# PSU.net
KiCad netlist of a schematic drawn in Altium Designer
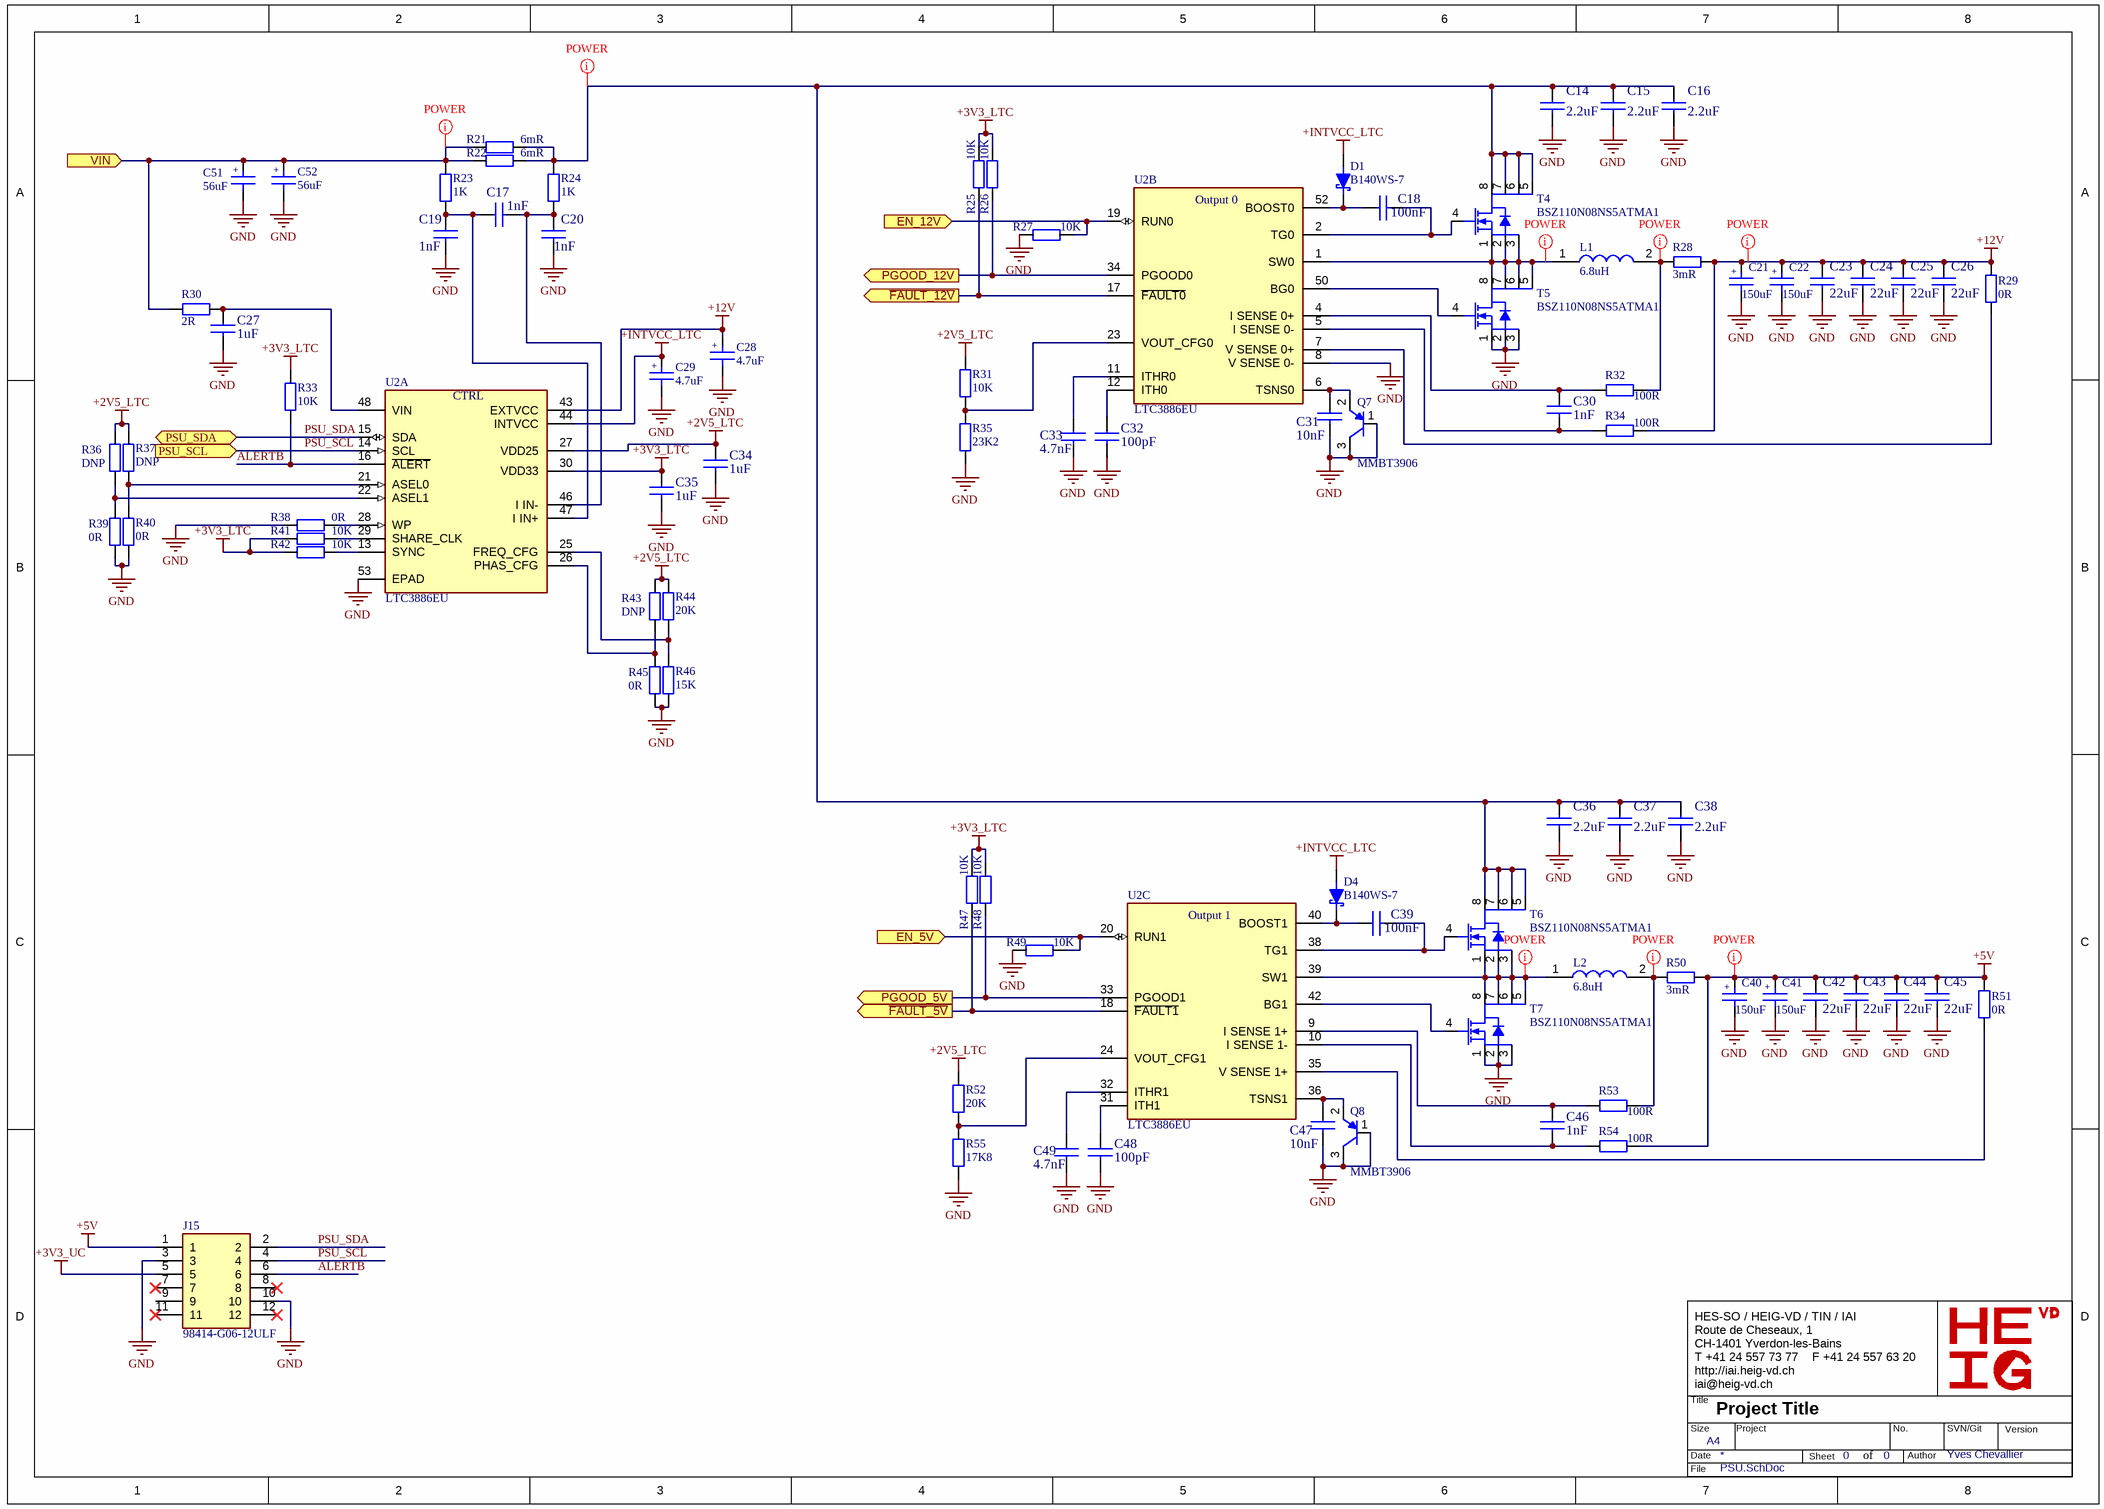
[diagram p0: PSU.SchDoc]

(export (version "E")
  (design (tool "Eeschema 10.0.6"))
  (components
    (comp (ref "C14")
      (value "2.2uF")
      (footprint "SM/C_0805")
      (description "CAP CER 2.2UF 25V X5R 0805")
      (fields (field (name "MANUFACTURER") "Samsung") (field (name "VOLTAGE") "25V"))
      (libsource (lib "Battery_PSU") (part "CAP CER 2.2UF 25V X5R 0805"))
    )
    (comp (ref "C15")
      (value "2.2uF")
      (footprint "SM/C_0805")
      (description "CAP CER 2.2UF 25V X5R 0805")
      (fields (field (name "MANUFACTURER") "Samsung") (field (name "VOLTAGE") "25V"))
      (libsource (lib "Battery_PSU") (part "CAP CER 2.2UF 25V X5R 0805"))
    )
    (comp (ref "C16")
      (value "2.2uF")
      (footprint "SM/C_0805")
      (description "CAP CER 2.2UF 25V X5R 0805")
      (fields (field (name "MANUFACTURER") "Samsung") (field (name "VOLTAGE") "25V"))
      (libsource (lib "Battery_PSU") (part "CAP CER 2.2UF 25V X5R 0805"))
    )
    (comp (ref "C17")
      (value "1nF")
      (footprint "SM/C_0603")
      (description "CAP CER 1NF 50V X7R 0603")
      (fields (field (name "MANUFACTURER") "Samsung") (field (name "VOLTAGE") "50V"))
      (libsource (lib "Battery_PSU") (part "CAP CER 1NF 50V X7R 0603"))
    )
    (comp (ref "C18")
      (value "100nF")
      (footprint "SM/C_0603")
      (description "CAP CER 0.1UF 50V X7R 0603")
      (fields (field (name "MANUFACTURER") "Samsung") (field (name "TOLERANCE") "10%"))
      (libsource (lib "Battery_PSU") (part "CAP CER 0.1UF 50V X7R 0603"))
    )
    (comp (ref "C19")
      (value "1nF")
      (footprint "SM/C_0603")
      (description "CAP CER 1NF 50V X7R 0603")
      (fields (field (name "MANUFACTURER") "Samsung") (field (name "VOLTAGE") "50V"))
      (libsource (lib "Battery_PSU") (part "CAP CER 1NF 50V X7R 0603"))
    )
    (comp (ref "C20")
      (value "1nF")
      (footprint "SM/C_0603")
      (description "CAP CER 1NF 50V X7R 0603")
      (fields (field (name "MANUFACTURER") "Samsung") (field (name "VOLTAGE") "50V"))
      (libsource (lib "Battery_PSU") (part "CAP CER 1NF 50V X7R 0603"))
    )
    (comp (ref "C21")
      (value "150uF")
      (footprint "SM/CT_7343_12_D")
      (description "CAP TANT 150UF 20% 25V 2924")
      (fields (field (name "TOLERANCE") "20%") (field (name "MANUFACTURER") "AVX"))
      (libsource (lib "Battery_PSU") (part "CAP TANT 150UF 20% 25V 2924"))
    )
    (comp (ref "C22")
      (value "150uF")
      (footprint "SM/CT_7343_12_D")
      (description "CAP TANT 150UF 20% 25V 2924")
      (fields (field (name "TOLERANCE") "20%") (field (name "MANUFACTURER") "AVX"))
      (libsource (lib "Battery_PSU") (part "CAP TANT 150UF 20% 25V 2924"))
    )
    (comp (ref "C23")
      (value "22uF")
      (footprint "SM/C_1210")
      (description "CAP CER 22UF 25V X5R 1210")
      (fields (field (name "MANUFACTURER") "Samsung") (field (name "VOLTAGE") "25V"))
      (libsource (lib "Battery_PSU") (part "CAP CER 22UF 25V X5R 1210"))
    )
    (comp (ref "C24")
      (value "22uF")
      (footprint "SM/C_1210")
      (description "CAP CER 22UF 25V X5R 1210")
      (fields (field (name "MANUFACTURER") "Samsung") (field (name "VOLTAGE") "25V"))
      (libsource (lib "Battery_PSU") (part "CAP CER 22UF 25V X5R 1210"))
    )
    (comp (ref "C25")
      (value "22uF")
      (footprint "SM/C_1210")
      (description "CAP CER 22UF 25V X5R 1210")
      (fields (field (name "MANUFACTURER") "Samsung") (field (name "VOLTAGE") "25V"))
      (libsource (lib "Battery_PSU") (part "CAP CER 22UF 25V X5R 1210"))
    )
    (comp (ref "C26")
      (value "22uF")
      (footprint "SM/C_1210")
      (description "CAP CER 22UF 25V X5R 1210")
      (fields (field (name "MANUFACTURER") "Samsung") (field (name "VOLTAGE") "25V"))
      (libsource (lib "Battery_PSU") (part "CAP CER 22UF 25V X5R 1210"))
    )
    (comp (ref "C27")
      (value "1uF")
      (footprint "SM/C_0805")
      (description "CAP CER 1UF 25V X7R 0805")
      (fields (field (name "MANUFACTURER") "Yageo") (field (name "VOLTAGE") "25V"))
      (libsource (lib "Battery_PSU") (part "CAP CER 1UF 25V X7R 0805"))
    )
    (comp (ref "C28")
      (value "4.7uF")
      (footprint "T_CAPMP3216X180N")
      (description "Capacitor TA 4.7uF 10V 20% 3216")
      (fields (field (name "TOLERANCE") "20%") (field (name "MANUFACTURER") "Kemet"))
      (libsource (lib "Battery_PSU") (part "C-TA-4.7uF-10V-20%-3216"))
    )
    (comp (ref "C29")
      (value "4.7uF")
      (footprint "T_CAPMP3216X180N")
      (description "Capacitor TA 4.7uF 10V 20% 3216")
      (fields (field (name "TOLERANCE") "20%") (field (name "MANUFACTURER") "Kemet"))
      (libsource (lib "Battery_PSU") (part "C-TA-4.7uF-10V-20%-3216"))
    )
    (comp (ref "C30")
      (value "1nF")
      (footprint "SM/C_0603")
      (description "CAP CER 1NF 50V X7R 0603")
      (fields (field (name "MANUFACTURER") "Samsung") (field (name "VOLTAGE") "50V"))
      (libsource (lib "Battery_PSU") (part "CAP CER 1NF 50V X7R 0603"))
    )
    (comp (ref "C31")
      (value "10nF")
      (footprint "SM/C_0603")
      (description "CAP CER 10NF 50V X7R 0603")
      (fields (field (name "MANUFACTURER") "Samsung") (field (name "VOLTAGE") "50V"))
      (libsource (lib "Battery_PSU") (part "CAP CER 10NF 50V X7R 0603"))
    )
    (comp (ref "C32")
      (value "100pF")
      (footprint "SM/C_0603")
      (description "CAP CER 100PF 50V C0G/NP0 0603")
      (fields (field (name "MANUFACTURER") "Samsung") (field (name "VOLTAGE") "50V"))
      (libsource (lib "Battery_PSU") (part "CAP CER 100PF 50V C0G/NP0 0603"))
    )
    (comp (ref "C33")
      (value "4.7nF")
      (footprint "SM/C_0603")
      (description "CAP CER 4700PF 50V X7R 0603")
      (fields (field (name "MANUFACTURER") "Kemet") (field (name "VOLTAGE") "50V"))
      (libsource (lib "Battery_PSU") (part "CAP CER 4700PF 50V X7R 0603"))
    )
    (comp (ref "C34")
      (value "1uF")
      (footprint "SM/C_0603")
      (description "CAP CER 1UF 10V X7R 0603")
      (fields (field (name "MANUFACTURER") "Samsung") (field (name "TOLERANCE") "10%"))
      (libsource (lib "Battery_PSU") (part "CAP CER 1UF 10V X7R 0603"))
    )
    (comp (ref "C35")
      (value "1uF")
      (footprint "SM/C_0603")
      (description "CAP CER 1UF 10V X7R 0603")
      (fields (field (name "MANUFACTURER") "Samsung") (field (name "TOLERANCE") "10%"))
      (libsource (lib "Battery_PSU") (part "CAP CER 1UF 10V X7R 0603"))
    )
    (comp (ref "C36")
      (value "2.2uF")
      (footprint "SM/C_0805")
      (description "CAP CER 2.2UF 25V X5R 0805")
      (fields (field (name "MANUFACTURER") "Samsung") (field (name "VOLTAGE") "25V"))
      (libsource (lib "Battery_PSU") (part "CAP CER 2.2UF 25V X5R 0805"))
    )
    (comp (ref "C37")
      (value "2.2uF")
      (footprint "SM/C_0805")
      (description "CAP CER 2.2UF 25V X5R 0805")
      (fields (field (name "MANUFACTURER") "Samsung") (field (name "VOLTAGE") "25V"))
      (libsource (lib "Battery_PSU") (part "CAP CER 2.2UF 25V X5R 0805"))
    )
    (comp (ref "C38")
      (value "2.2uF")
      (footprint "SM/C_0805")
      (description "CAP CER 2.2UF 25V X5R 0805")
      (fields (field (name "MANUFACTURER") "Samsung") (field (name "VOLTAGE") "25V"))
      (libsource (lib "Battery_PSU") (part "CAP CER 2.2UF 25V X5R 0805"))
    )
    (comp (ref "C39")
      (value "100nF")
      (footprint "SM/C_0603")
      (description "CAP CER 0.1UF 50V X7R 0603")
      (fields (field (name "MANUFACTURER") "Samsung") (field (name "TOLERANCE") "10%"))
      (libsource (lib "Battery_PSU") (part "CAP CER 0.1UF 50V X7R 0603"))
    )
    (comp (ref "C40")
      (value "150uF")
      (footprint "SM/CT_7343_12_D")
      (description "CAP TANT 150UF 20% 25V 2924")
      (fields (field (name "TOLERANCE") "20%") (field (name "MANUFACTURER") "AVX"))
      (libsource (lib "Battery_PSU") (part "CAP TANT 150UF 20% 25V 2924"))
    )
    (comp (ref "C41")
      (value "150uF")
      (footprint "SM/CT_7343_12_D")
      (description "CAP TANT 150UF 20% 25V 2924")
      (fields (field (name "TOLERANCE") "20%") (field (name "MANUFACTURER") "AVX"))
      (libsource (lib "Battery_PSU") (part "CAP TANT 150UF 20% 25V 2924"))
    )
    (comp (ref "C42")
      (value "22uF")
      (footprint "SM/C_1210")
      (description "CAP CER 22UF 25V X5R 1210")
      (fields (field (name "MANUFACTURER") "Samsung") (field (name "VOLTAGE") "25V"))
      (libsource (lib "Battery_PSU") (part "CAP CER 22UF 25V X5R 1210"))
    )
    (comp (ref "C43")
      (value "22uF")
      (footprint "SM/C_1210")
      (description "CAP CER 22UF 25V X5R 1210")
      (fields (field (name "MANUFACTURER") "Samsung") (field (name "VOLTAGE") "25V"))
      (libsource (lib "Battery_PSU") (part "CAP CER 22UF 25V X5R 1210"))
    )
    (comp (ref "C44")
      (value "22uF")
      (footprint "SM/C_1210")
      (description "CAP CER 22UF 25V X5R 1210")
      (fields (field (name "MANUFACTURER") "Samsung") (field (name "VOLTAGE") "25V"))
      (libsource (lib "Battery_PSU") (part "CAP CER 22UF 25V X5R 1210"))
    )
    (comp (ref "C45")
      (value "22uF")
      (footprint "SM/C_1210")
      (description "CAP CER 22UF 25V X5R 1210")
      (fields (field (name "MANUFACTURER") "Samsung") (field (name "VOLTAGE") "25V"))
      (libsource (lib "Battery_PSU") (part "CAP CER 22UF 25V X5R 1210"))
    )
    (comp (ref "C46")
      (value "1nF")
      (footprint "SM/C_0603")
      (description "CAP CER 1NF 50V X7R 0603")
      (fields (field (name "MANUFACTURER") "Samsung") (field (name "VOLTAGE") "50V"))
      (libsource (lib "Battery_PSU") (part "CAP CER 1NF 50V X7R 0603"))
    )
    (comp (ref "C47")
      (value "10nF")
      (footprint "SM/C_0603")
      (description "CAP CER 10NF 50V X7R 0603")
      (fields (field (name "MANUFACTURER") "Samsung") (field (name "VOLTAGE") "50V"))
      (libsource (lib "Battery_PSU") (part "CAP CER 10NF 50V X7R 0603"))
    )
    (comp (ref "C48")
      (value "100pF")
      (footprint "SM/C_0603")
      (description "CAP CER 100PF 50V C0G/NP0 0603")
      (fields (field (name "MANUFACTURER") "Samsung") (field (name "VOLTAGE") "50V"))
      (libsource (lib "Battery_PSU") (part "CAP CER 100PF 50V C0G/NP0 0603"))
    )
    (comp (ref "C49")
      (value "4.7nF")
      (footprint "SM/C_0603")
      (description "CAP CER 4700PF 50V X7R 0603")
      (fields (field (name "MANUFACTURER") "Kemet") (field (name "VOLTAGE") "50V"))
      (libsource (lib "Battery_PSU") (part "CAP CER 4700PF 50V X7R 0603"))
    )
    (comp (ref "C51")
      (value "56uF")
      (footprint "SM/C SIZE F12")
      (description "HYBRID POLYMER, SMD, 63V, 56UF,")
      (fields (field (name "TOLERANCE") "20%") (field (name "MANUFACTURER") "Kemet"))
      (libsource (lib "Battery_PSU") (part "HYBRID POLYMER, SMD, 63V, 56UF,"))
    )
    (comp (ref "C52")
      (value "56uF")
      (footprint "SM/C SIZE F12")
      (description "HYBRID POLYMER, SMD, 63V, 56UF,")
      (fields (field (name "TOLERANCE") "20%") (field (name "MANUFACTURER") "Kemet"))
      (libsource (lib "Battery_PSU") (part "HYBRID POLYMER, SMD, 63V, 56UF,"))
    )
    (comp (ref "D1")
      (value "B140WS-7")
      (footprint "SM/D_SOD323_A1C2 (SC-76)")
      (description "DIODE SCHOTTKY 40V 1A SOD323")
      (fields (field (name "MANUFACTURER") "Diodes Incorporated"))
      (libsource (lib "Battery_PSU") (part "DIODE SCHOTTKY 40V 1A SOD323"))
    )
    (comp (ref "D4")
      (value "B140WS-7")
      (footprint "SM/D_SOD323_A1C2 (SC-76)")
      (description "DIODE SCHOTTKY 40V 1A SOD323")
      (fields (field (name "MANUFACTURER") "Diodes Incorporated"))
      (libsource (lib "Battery_PSU") (part "DIODE SCHOTTKY 40V 1A SOD323"))
    )
    (comp (ref "J15")
      (value "98414-G06-12ULF")
      (footprint "98414G0612ULF")
      (description "CONN HEADER VERT 12POS 2MM")
      (fields (field (name "MANUFACTURER") "Amphenol"))
      (libsource (lib "Battery_PSU") (part "CONN HEADER VERT 12POS 2MM"))
    )
    (comp (ref "L1")
      (value "6.8uH")
      (footprint "SamacSys:WE-HCI_189023")
      (description "FIXED IND 6.8UH 18.5A 4.1MOHM SM")
      (fields (field (name "MANUFACTURER") "Wurth Elektronik"))
      (libsource (lib "Battery_PSU") (part "FIXED IND 6.8UH 18.5A 4.1MOHM SM"))
    )
    (comp (ref "L2")
      (value "6.8uH")
      (footprint "SamacSys:WE-HCI_189023")
      (description "FIXED IND 6.8UH 18.5A 4.1MOHM SM")
      (fields (field (name "MANUFACTURER") "Wurth Elektronik"))
      (libsource (lib "Battery_PSU") (part "FIXED IND 6.8UH 18.5A 4.1MOHM SM"))
    )
    (comp (ref "Q7")
      (value "MMBT3906")
      (footprint "SOT23")
      (description "TRANSISTOR, PNP, -40V, -0.2A, 10")
      (fields (field (name "MANUFACTURER") "Taiwan Semiconductor"))
      (libsource (lib "Battery_PSU") (part "TRANSISTOR, PNP, -40V, -0.2A, 10"))
    )
    (comp (ref "Q8")
      (value "MMBT3906")
      (footprint "SOT23")
      (description "TRANSISTOR, PNP, -40V, -0.2A, 10")
      (fields (field (name "MANUFACTURER") "Taiwan Semiconductor"))
      (libsource (lib "Battery_PSU") (part "TRANSISTOR, PNP, -40V, -0.2A, 10"))
    )
    (comp (ref "R21")
      (value "6mR")
      (footprint "SM/R_2512")
      (description "METAL CURRENT SENSOR 2512 1% 100")
      (fields (field (name "MANUFACTURER") "Yageo") (field (name "POWER") "2W"))
      (libsource (lib "Battery_PSU") (part "METAL CURRENT SENSOR 2512 1% 100"))
    )
    (comp (ref "R22")
      (value "6mR")
      (footprint "SM/R_2512")
      (description "METAL CURRENT SENSOR 2512 1% 100")
      (fields (field (name "MANUFACTURER") "Yageo") (field (name "POWER") "2W"))
      (libsource (lib "Battery_PSU") (part "METAL CURRENT SENSOR 2512 1% 100"))
    )
    (comp (ref "R23")
      (value "1K")
      (footprint "SM/R_0603")
      (description "RES SMD 1K OHM 1% 1/10W 0603")
      (fields (field (name "MANUFACTURER") "Yageo") (field (name "POWER") "100mW"))
      (libsource (lib "Battery_PSU") (part "RES SMD 1K OHM 1% 1/10W 0603"))
    )
    (comp (ref "R24")
      (value "1K")
      (footprint "SM/R_0603")
      (description "RES SMD 1K OHM 1% 1/10W 0603")
      (fields (field (name "MANUFACTURER") "Yageo") (field (name "POWER") "100mW"))
      (libsource (lib "Battery_PSU") (part "RES SMD 1K OHM 1% 1/10W 0603"))
    )
    (comp (ref "R25")
      (value "10K")
      (footprint "SM/R_0603")
      (description "Résistance 0603 100mW 1% 10K")
      (fields (field (name "MANUFACTURER") "Yageo") (field (name "POWER") "100mW"))
      (libsource (lib "Battery_PSU") (part "RES SMD 10K OHM 1% 1/10W 0603"))
    )
    (comp (ref "R26")
      (value "10K")
      (footprint "SM/R_0603")
      (description "Résistance 0603 100mW 1% 10K")
      (fields (field (name "MANUFACTURER") "Yageo") (field (name "POWER") "100mW"))
      (libsource (lib "Battery_PSU") (part "RES SMD 10K OHM 1% 1/10W 0603"))
    )
    (comp (ref "R27")
      (value "10K")
      (footprint "SM/R_0603")
      (description "Résistance 0603 100mW 1% 10K")
      (fields (field (name "MANUFACTURER") "Yageo") (field (name "POWER") "100mW"))
      (libsource (lib "Battery_PSU") (part "RES SMD 10K OHM 1% 1/10W 0603"))
    )
    (comp (ref "R28")
      (value "3mR")
      (footprint "SM/R_1210")
      (description "RES 0.003 OHM 5% 1W 1210")
      (fields (field (name "MANUFACTURER") "Rohm") (field (name "POWER") "1W"))
      (libsource (lib "Battery_PSU") (part "RES 0.003 OHM 5% 1W 1210"))
    )
    (comp (ref "R29")
      (value "0R")
      (footprint "SM/R_0603")
      (description "RES SMD 0 OHM JUMPER 1/10W 0603")
      (fields (field (name "MANUFACTURER") "Yageo") (field (name "POWER") "100mW"))
      (libsource (lib "Battery_PSU") (part "RES SMD 0 OHM JUMPER 1/10W 0603"))
    )
    (comp (ref "R30")
      (value "2R")
      (footprint "SM/R_0603")
      (description "RES 2 OHM 1% 1/10W 0603")
      (fields (field (name "MANUFACTURER") "Yageo") (field (name "POWER") "100mW"))
      (libsource (lib "Battery_PSU") (part "RES 2 OHM 1% 1/10W 0603"))
    )
    (comp (ref "R31")
      (value "10K")
      (footprint "SM/R_0603")
      (description "Résistance 0603 100mW 1% 10K")
      (fields (field (name "MANUFACTURER") "Yageo") (field (name "POWER") "100mW"))
      (libsource (lib "Battery_PSU") (part "RES SMD 10K OHM 1% 1/10W 0603"))
    )
    (comp (ref "R32")
      (value "100R")
      (footprint "SM/R_0603")
      (description "RES 100 OHM 1% 1/10W 0603")
      (fields (field (name "MANUFACTURER") "Yageo") (field (name "POWER") "100mW"))
      (libsource (lib "Battery_PSU") (part "RES 100 OHM 1% 1/10W 0603"))
    )
    (comp (ref "R33")
      (value "10K")
      (footprint "SM/R_0603")
      (description "Résistance 0603 100mW 1% 10K")
      (fields (field (name "MANUFACTURER") "Yageo") (field (name "POWER") "100mW"))
      (libsource (lib "Battery_PSU") (part "RES SMD 10K OHM 1% 1/10W 0603"))
    )
    (comp (ref "R34")
      (value "100R")
      (footprint "SM/R_0603")
      (description "RES 100 OHM 1% 1/10W 0603")
      (fields (field (name "MANUFACTURER") "Yageo") (field (name "POWER") "100mW"))
      (libsource (lib "Battery_PSU") (part "RES 100 OHM 1% 1/10W 0603"))
    )
    (comp (ref "R35")
      (value "23K2")
      (footprint "SM/R_0603")
      (description "RES 23.2K OHM 1% 1/10W 0603")
      (fields (field (name "MANUFACTURER") "Yageo") (field (name "POWER") "100mW"))
      (libsource (lib "Battery_PSU") (part "RES 23.2K OHM 1% 1/10W 0603"))
    )
    (comp (ref "R36")
      (value "DNP")
      (footprint "SM/R_0603")
      (description "RES SMD DNP JUMPER 1/10W 0603")
      (libsource (lib "Battery_PSU") (part "RES SMD DNP JUMPER 1/10W 0603"))
    )
    (comp (ref "R37")
      (value "DNP")
      (footprint "SM/R_0603")
      (description "RES SMD DNP JUMPER 1/10W 0603")
      (libsource (lib "Battery_PSU") (part "RES SMD DNP JUMPER 1/10W 0603"))
    )
    (comp (ref "R38")
      (value "0R")
      (footprint "SM/R_0603")
      (description "RES SMD 0 OHM JUMPER 1/10W 0603")
      (fields (field (name "MANUFACTURER") "Yageo") (field (name "POWER") "100mW"))
      (libsource (lib "Battery_PSU") (part "RES SMD 0 OHM JUMPER 1/10W 0603"))
    )
    (comp (ref "R39")
      (value "0R")
      (footprint "SM/R_0603")
      (description "RES SMD 0 OHM JUMPER 1/10W 0603")
      (fields (field (name "MANUFACTURER") "Yageo") (field (name "POWER") "100mW"))
      (libsource (lib "Battery_PSU") (part "RES SMD 0 OHM JUMPER 1/10W 0603"))
    )
    (comp (ref "R40")
      (value "0R")
      (footprint "SM/R_0603")
      (description "RES SMD 0 OHM JUMPER 1/10W 0603")
      (fields (field (name "MANUFACTURER") "Yageo") (field (name "POWER") "100mW"))
      (libsource (lib "Battery_PSU") (part "RES SMD 0 OHM JUMPER 1/10W 0603"))
    )
    (comp (ref "R41")
      (value "10K")
      (footprint "SM/R_0603")
      (description "Résistance 0603 100mW 1% 10K")
      (fields (field (name "MANUFACTURER") "Yageo") (field (name "POWER") "100mW"))
      (libsource (lib "Battery_PSU") (part "RES SMD 10K OHM 1% 1/10W 0603"))
    )
    (comp (ref "R42")
      (value "10K")
      (footprint "SM/R_0603")
      (description "Résistance 0603 100mW 1% 10K")
      (fields (field (name "MANUFACTURER") "Yageo") (field (name "POWER") "100mW"))
      (libsource (lib "Battery_PSU") (part "RES SMD 10K OHM 1% 1/10W 0603"))
    )
    (comp (ref "R43")
      (value "DNP")
      (footprint "SM/R_0603")
      (description "RES SMD DNP JUMPER 1/10W 0603")
      (libsource (lib "Battery_PSU") (part "RES SMD DNP JUMPER 1/10W 0603"))
    )
    (comp (ref "R44")
      (value "20K")
      (footprint "SM/R_0603")
      (description "RES 20K OHM 1% 1/10W 0603")
      (fields (field (name "MANUFACTURER") "Yageo") (field (name "POWER") "100mW"))
      (libsource (lib "Battery_PSU") (part "RES 20K OHM 1% 1/10W 0603"))
    )
    (comp (ref "R45")
      (value "0R")
      (footprint "SM/R_0603")
      (description "RES SMD 0 OHM JUMPER 1/10W 0603")
      (fields (field (name "MANUFACTURER") "Yageo") (field (name "POWER") "100mW"))
      (libsource (lib "Battery_PSU") (part "RES SMD 0 OHM JUMPER 1/10W 0603"))
    )
    (comp (ref "R46")
      (value "15K")
      (footprint "SM/R_0603")
      (description "RES 15K OHM 1% 1/10W 0603")
      (fields (field (name "MANUFACTURER") "Yageo") (field (name "POWER") "100mW"))
      (libsource (lib "Battery_PSU") (part "RES 15K OHM 1% 1/10W 0603"))
    )
    (comp (ref "R47")
      (value "10K")
      (footprint "SM/R_0603")
      (description "Résistance 0603 100mW 1% 10K")
      (fields (field (name "MANUFACTURER") "Yageo") (field (name "POWER") "100mW"))
      (libsource (lib "Battery_PSU") (part "RES SMD 10K OHM 1% 1/10W 0603"))
    )
    (comp (ref "R48")
      (value "10K")
      (footprint "SM/R_0603")
      (description "Résistance 0603 100mW 1% 10K")
      (fields (field (name "MANUFACTURER") "Yageo") (field (name "POWER") "100mW"))
      (libsource (lib "Battery_PSU") (part "RES SMD 10K OHM 1% 1/10W 0603"))
    )
    (comp (ref "R49")
      (value "10K")
      (footprint "SM/R_0603")
      (description "Résistance 0603 100mW 1% 10K")
      (fields (field (name "MANUFACTURER") "Yageo") (field (name "POWER") "100mW"))
      (libsource (lib "Battery_PSU") (part "RES SMD 10K OHM 1% 1/10W 0603"))
    )
    (comp (ref "R50")
      (value "3mR")
      (footprint "SM/R_1210")
      (description "RES 0.003 OHM 5% 1W 1210")
      (fields (field (name "MANUFACTURER") "Rohm") (field (name "POWER") "1W"))
      (libsource (lib "Battery_PSU") (part "RES 0.003 OHM 5% 1W 1210"))
    )
    (comp (ref "R51")
      (value "0R")
      (footprint "SM/R_0603")
      (description "RES SMD 0 OHM JUMPER 1/10W 0603")
      (fields (field (name "MANUFACTURER") "Yageo") (field (name "POWER") "100mW"))
      (libsource (lib "Battery_PSU") (part "RES SMD 0 OHM JUMPER 1/10W 0603"))
    )
    (comp (ref "R52")
      (value "20K")
      (footprint "SM/R_0603")
      (description "RES 20K OHM 1% 1/10W 0603")
      (fields (field (name "MANUFACTURER") "Yageo") (field (name "POWER") "100mW"))
      (libsource (lib "Battery_PSU") (part "RES 20K OHM 1% 1/10W 0603"))
    )
    (comp (ref "R53")
      (value "100R")
      (footprint "SM/R_0603")
      (description "RES 100 OHM 1% 1/10W 0603")
      (fields (field (name "MANUFACTURER") "Yageo") (field (name "POWER") "100mW"))
      (libsource (lib "Battery_PSU") (part "RES 100 OHM 1% 1/10W 0603"))
    )
    (comp (ref "R54")
      (value "100R")
      (footprint "SM/R_0603")
      (description "RES 100 OHM 1% 1/10W 0603")
      (fields (field (name "MANUFACTURER") "Yageo") (field (name "POWER") "100mW"))
      (libsource (lib "Battery_PSU") (part "RES 100 OHM 1% 1/10W 0603"))
    )
    (comp (ref "R55")
      (value "17K8")
      (footprint "SM/R_0603")
      (description "RES 17.8K OHM 1% 1/10W 0603")
      (fields (field (name "MANUFACTURER") "Yageo") (field (name "POWER") "100mW"))
      (libsource (lib "Battery_PSU") (part "RES 17.8K OHM 1% 1/10W 0603"))
    )
    (comp (ref "T4")
      (value "BSZ110N08NS5ATMA1")
      (footprint "BSZ110N08NS5ATMA1")
      (description "MOSFET N-CH 80V 40A TSDSON")
      (libsource (lib "Battery_PSU") (part "MOSFET N-CH 80V 40A TSDSON"))
    )
    (comp (ref "T5")
      (value "BSZ110N08NS5ATMA1")
      (footprint "BSZ110N08NS5ATMA1")
      (description "MOSFET N-CH 80V 40A TSDSON")
      (libsource (lib "Battery_PSU") (part "MOSFET N-CH 80V 40A TSDSON"))
    )
    (comp (ref "T6")
      (value "BSZ110N08NS5ATMA1")
      (footprint "BSZ110N08NS5ATMA1")
      (description "MOSFET N-CH 80V 40A TSDSON")
      (libsource (lib "Battery_PSU") (part "MOSFET N-CH 80V 40A TSDSON"))
    )
    (comp (ref "T7")
      (value "BSZ110N08NS5ATMA1")
      (footprint "BSZ110N08NS5ATMA1")
      (description "MOSFET N-CH 80V 40A TSDSON")
      (libsource (lib "Battery_PSU") (part "MOSFET N-CH 80V 40A TSDSON"))
    )
    (comp (ref "U2")
      (value "LTC3886EU")
      (footprint "UKG_52_ADI")
      (description "IC REG CTRLR BUCK PMBUS 52QFN")
      (fields (field (name "MANUFACTURER") "Analog Devices"))
      (libsource (lib "Battery_PSU") (part "IC REG CTRLR BUCK PMBUS 52QFN"))
    )
  )
  (nets
    (net (code "1") (name "+2V5_LTC") (class "Default")
      (node (ref "C34") (pin "1") (pinfunction "1_1") (pintype "passive"))
      (node (ref "R31") (pin "2") (pinfunction "2_2") (pintype "passive"))
      (node (ref "R36") (pin "2") (pinfunction "2_2") (pintype "passive"))
      (node (ref "R37") (pin "2") (pinfunction "2_2") (pintype "passive"))
      (node (ref "R43") (pin "2") (pinfunction "2_2") (pintype "passive"))
      (node (ref "R44") (pin "1") (pinfunction "1_1") (pintype "passive"))
      (node (ref "R52") (pin "1") (pinfunction "1_1") (pintype "passive"))
      (node (ref "U2") (pin "27") (pinfunction "VDD25_27") (pintype "power_in"))
    )
    (net (code "2") (name "+3V3_LTC") (class "Default")
      (node (ref "C35") (pin "1") (pinfunction "1_1") (pintype "passive"))
      (node (ref "R25") (pin "1") (pinfunction "1_1") (pintype "passive"))
      (node (ref "R26") (pin "1") (pinfunction "1_1") (pintype "passive"))
      (node (ref "R33") (pin "2") (pinfunction "2_2") (pintype "passive"))
      (node (ref "R41") (pin "1") (pinfunction "1_1") (pintype "passive"))
      (node (ref "R42") (pin "1") (pinfunction "1_1") (pintype "passive"))
      (node (ref "R47") (pin "1") (pinfunction "1_1") (pintype "passive"))
      (node (ref "R48") (pin "1") (pinfunction "1_1") (pintype "passive"))
      (node (ref "U2") (pin "30") (pinfunction "VDD33_30") (pintype "power_in"))
    )
    (net (code "3") (name "+3V3_UC") (class "Default")
      (node (ref "J15") (pin "5") (pinfunction "5_5") (pintype "passive"))
    )
    (net (code "4") (name "+5V") (class "Default")
      (node (ref "C40") (pin "1") (pinfunction "1_1") (pintype "passive"))
      (node (ref "C41") (pin "1") (pinfunction "1_1") (pintype "passive"))
      (node (ref "C42") (pin "1") (pinfunction "1_1") (pintype "passive"))
      (node (ref "C43") (pin "1") (pinfunction "1_1") (pintype "passive"))
      (node (ref "C44") (pin "1") (pinfunction "1_1") (pintype "passive"))
      (node (ref "C45") (pin "1") (pinfunction "1_1") (pintype "passive"))
      (node (ref "J15") (pin "1") (pinfunction "1_1") (pintype "passive"))
      (node (ref "R50") (pin "2") (pinfunction "2_2") (pintype "passive"))
      (node (ref "R51") (pin "2") (pinfunction "2_2") (pintype "passive"))
      (node (ref "R54") (pin "2") (pinfunction "2_2") (pintype "passive"))
    )
    (net (code "5") (name "+12V") (class "Default")
      (node (ref "C21") (pin "1") (pinfunction "1_1") (pintype "passive"))
      (node (ref "C22") (pin "1") (pinfunction "1_1") (pintype "passive"))
      (node (ref "C23") (pin "1") (pinfunction "1_1") (pintype "passive"))
      (node (ref "C24") (pin "1") (pinfunction "1_1") (pintype "passive"))
      (node (ref "C25") (pin "1") (pinfunction "1_1") (pintype "passive"))
      (node (ref "C26") (pin "1") (pinfunction "1_1") (pintype "passive"))
      (node (ref "C28") (pin "1") (pinfunction "1_1") (pintype "passive"))
      (node (ref "R28") (pin "2") (pinfunction "2_2") (pintype "passive"))
      (node (ref "R29") (pin "2") (pinfunction "2_2") (pintype "passive"))
      (node (ref "R34") (pin "2") (pinfunction "2_2") (pintype "passive"))
      (node (ref "U2") (pin "43") (pinfunction "EXTVCC_43") (pintype "power_in"))
    )
    (net (code "6") (name "+INTVCC_LTC") (class "Default")
      (node (ref "C29") (pin "1") (pinfunction "1_1") (pintype "passive"))
      (node (ref "D1") (pin "1") (pinfunction "A_1") (pintype "passive"))
      (node (ref "D4") (pin "1") (pinfunction "A_1") (pintype "passive"))
      (node (ref "U2") (pin "44") (pinfunction "INTVCC_44") (pintype "power_in"))
    )
    (net (code "7") (name "/ALERTB") (class "Default")
      (node (ref "J15") (pin "6") (pinfunction "6_6") (pintype "passive"))
      (node (ref "R33") (pin "1") (pinfunction "1_1") (pintype "passive"))
      (node (ref "U2") (pin "16") (pinfunction "ALERT_16") (pintype "open_collector"))
    )
    (net (code "8") (name "/EN_5V") (class "Default")
      (node (ref "R49") (pin "1") (pinfunction "1_1") (pintype "passive"))
      (node (ref "U2") (pin "20") (pinfunction "RUN1_20") (pintype "bidirectional"))
    )
    (net (code "9") (name "/EN_12V") (class "Default")
      (node (ref "R27") (pin "1") (pinfunction "1_1") (pintype "passive"))
      (node (ref "U2") (pin "19") (pinfunction "RUN0_19") (pintype "bidirectional"))
    )
    (net (code "10") (name "/FAULT_5V") (class "Default")
      (node (ref "R47") (pin "2") (pinfunction "2_2") (pintype "passive"))
      (node (ref "U2") (pin "18") (pinfunction "FAULT1_18") (pintype "open_collector"))
    )
    (net (code "11") (name "/FAULT_12V") (class "Default")
      (node (ref "R25") (pin "2") (pinfunction "2_2") (pintype "passive"))
      (node (ref "U2") (pin "17") (pinfunction "FAULT0_17") (pintype "open_collector"))
    )
    (net (code "12") (name "/PGOOD_5V") (class "Default")
      (node (ref "R48") (pin "2") (pinfunction "2_2") (pintype "passive"))
      (node (ref "U2") (pin "33") (pinfunction "PGOOD1_33") (pintype "open_collector"))
    )
    (net (code "13") (name "/PGOOD_12V") (class "Default")
      (node (ref "R26") (pin "2") (pinfunction "2_2") (pintype "passive"))
      (node (ref "U2") (pin "34") (pinfunction "PGOOD0_34") (pintype "open_collector"))
    )
    (net (code "14") (name "/PSU_SCL") (class "Default")
      (node (ref "J15") (pin "4") (pinfunction "4_4") (pintype "passive"))
      (node (ref "U2") (pin "14") (pinfunction "SCL_14") (pintype "input"))
    )
    (net (code "15") (name "/PSU_SDA") (class "Default")
      (node (ref "J15") (pin "2") (pinfunction "2_2") (pintype "passive"))
      (node (ref "U2") (pin "15") (pinfunction "SDA_15") (pintype "bidirectional"))
    )
    (net (code "16") (name "/VIN") (class "Default")
      (node (ref "C51") (pin "1") (pinfunction "1_1") (pintype "passive"))
      (node (ref "C52") (pin "1") (pinfunction "1_1") (pintype "passive"))
      (node (ref "R21") (pin "1") (pinfunction "1_1") (pintype "passive"))
      (node (ref "R22") (pin "1") (pinfunction "1_1") (pintype "passive"))
      (node (ref "R23") (pin "1") (pinfunction "1_1") (pintype "passive"))
      (node (ref "R30") (pin "1") (pinfunction "1_1") (pintype "passive"))
    )
    (net (code "17") (name "GND") (class "Default")
      (node (ref "C14") (pin "2") (pinfunction "2_2") (pintype "passive"))
      (node (ref "C15") (pin "2") (pinfunction "2_2") (pintype "passive"))
      (node (ref "C16") (pin "2") (pinfunction "2_2") (pintype "passive"))
      (node (ref "C19") (pin "2") (pinfunction "2_2") (pintype "passive"))
      (node (ref "C20") (pin "2") (pinfunction "2_2") (pintype "passive"))
      (node (ref "C21") (pin "2") (pinfunction "2_2") (pintype "passive"))
      (node (ref "C22") (pin "2") (pinfunction "2_2") (pintype "passive"))
      (node (ref "C23") (pin "2") (pinfunction "2_2") (pintype "passive"))
      (node (ref "C24") (pin "2") (pinfunction "2_2") (pintype "passive"))
      (node (ref "C25") (pin "2") (pinfunction "2_2") (pintype "passive"))
      (node (ref "C26") (pin "2") (pinfunction "2_2") (pintype "passive"))
      (node (ref "C27") (pin "2") (pinfunction "2_2") (pintype "passive"))
      (node (ref "C28") (pin "2") (pinfunction "2_2") (pintype "passive"))
      (node (ref "C29") (pin "2") (pinfunction "2_2") (pintype "passive"))
      (node (ref "C31") (pin "2") (pinfunction "2_2") (pintype "passive"))
      (node (ref "C32") (pin "2") (pinfunction "2_2") (pintype "passive"))
      (node (ref "C33") (pin "2") (pinfunction "2_2") (pintype "passive"))
      (node (ref "C34") (pin "2") (pinfunction "2_2") (pintype "passive"))
      (node (ref "C35") (pin "2") (pinfunction "2_2") (pintype "passive"))
      (node (ref "C36") (pin "2") (pinfunction "2_2") (pintype "passive"))
      (node (ref "C37") (pin "2") (pinfunction "2_2") (pintype "passive"))
      (node (ref "C38") (pin "2") (pinfunction "2_2") (pintype "passive"))
      (node (ref "C40") (pin "2") (pinfunction "2_2") (pintype "passive"))
      (node (ref "C41") (pin "2") (pinfunction "2_2") (pintype "passive"))
      (node (ref "C42") (pin "2") (pinfunction "2_2") (pintype "passive"))
      (node (ref "C43") (pin "2") (pinfunction "2_2") (pintype "passive"))
      (node (ref "C44") (pin "2") (pinfunction "2_2") (pintype "passive"))
      (node (ref "C45") (pin "2") (pinfunction "2_2") (pintype "passive"))
      (node (ref "C47") (pin "2") (pinfunction "2_2") (pintype "passive"))
      (node (ref "C48") (pin "2") (pinfunction "2_2") (pintype "passive"))
      (node (ref "C49") (pin "2") (pinfunction "2_2") (pintype "passive"))
      (node (ref "C51") (pin "2") (pinfunction "2_2") (pintype "passive"))
      (node (ref "C52") (pin "2") (pinfunction "2_2") (pintype "passive"))
      (node (ref "J15") (pin "10") (pinfunction "10_10") (pintype "passive"))
      (node (ref "J15") (pin "3") (pinfunction "3_3") (pintype "passive"))
      (node (ref "Q7") (pin "1") (pinfunction "B_1") (pintype "passive"))
      (node (ref "Q7") (pin "3") (pinfunction "C_3") (pintype "passive"))
      (node (ref "Q8") (pin "1") (pinfunction "B_1") (pintype "passive"))
      (node (ref "Q8") (pin "3") (pinfunction "C_3") (pintype "passive"))
      (node (ref "R27") (pin "2") (pinfunction "2_2") (pintype "passive"))
      (node (ref "R35") (pin "2") (pinfunction "2_2") (pintype "passive"))
      (node (ref "R38") (pin "2") (pinfunction "2_2") (pintype "passive"))
      (node (ref "R39") (pin "1") (pinfunction "1_1") (pintype "passive"))
      (node (ref "R40") (pin "1") (pinfunction "1_1") (pintype "passive"))
      (node (ref "R45") (pin "1") (pinfunction "1_1") (pintype "passive"))
      (node (ref "R46") (pin "2") (pinfunction "2_2") (pintype "passive"))
      (node (ref "R49") (pin "2") (pinfunction "2_2") (pintype "passive"))
      (node (ref "R55") (pin "2") (pinfunction "2_2") (pintype "passive"))
      (node (ref "T5") (pin "1") (pinfunction "S_1") (pintype "passive"))
      (node (ref "T5") (pin "2") (pinfunction "S_2") (pintype "passive"))
      (node (ref "T5") (pin "3") (pinfunction "S_3") (pintype "passive"))
      (node (ref "T7") (pin "1") (pinfunction "S_1") (pintype "passive"))
      (node (ref "T7") (pin "2") (pinfunction "S_2") (pintype "passive"))
      (node (ref "T7") (pin "3") (pinfunction "S_3") (pintype "passive"))
      (node (ref "U2") (pin "53") (pinfunction "EPAD_53") (pintype "power_in"))
      (node (ref "U2") (pin "8") (pinfunction "V_SENSE_0-_8") (pintype "passive"))
    )
    (net (code "18") (name "Net-(C14-Pad1)") (class "Default")
      (node (ref "C14") (pin "1") (pinfunction "1_1") (pintype "passive"))
      (node (ref "C15") (pin "1") (pinfunction "1_1") (pintype "passive"))
      (node (ref "C16") (pin "1") (pinfunction "1_1") (pintype "passive"))
      (node (ref "C36") (pin "1") (pinfunction "1_1") (pintype "passive"))
      (node (ref "C37") (pin "1") (pinfunction "1_1") (pintype "passive"))
      (node (ref "C38") (pin "1") (pinfunction "1_1") (pintype "passive"))
      (node (ref "R21") (pin "2") (pinfunction "2_2") (pintype "passive"))
      (node (ref "R22") (pin "2") (pinfunction "2_2") (pintype "passive"))
      (node (ref "R24") (pin "1") (pinfunction "1_1") (pintype "passive"))
      (node (ref "T4") (pin "5") (pinfunction "D_5") (pintype "passive"))
      (node (ref "T4") (pin "6") (pinfunction "D_6") (pintype "passive"))
      (node (ref "T4") (pin "7") (pinfunction "D_7") (pintype "passive"))
      (node (ref "T4") (pin "8") (pinfunction "D_8") (pintype "passive"))
      (node (ref "T6") (pin "5") (pinfunction "D_5") (pintype "passive"))
      (node (ref "T6") (pin "6") (pinfunction "D_6") (pintype "passive"))
      (node (ref "T6") (pin "7") (pinfunction "D_7") (pintype "passive"))
      (node (ref "T6") (pin "8") (pinfunction "D_8") (pintype "passive"))
    )
    (net (code "19") (name "Net-(D1-C)") (class "Default")
      (node (ref "C18") (pin "1") (pinfunction "1_1") (pintype "passive"))
      (node (ref "D1") (pin "2") (pinfunction "C_2") (pintype "passive"))
      (node (ref "U2") (pin "52") (pinfunction "BOOST0_52") (pintype "power_in"))
    )
    (net (code "20") (name "Net-(D4-C)") (class "Default")
      (node (ref "C39") (pin "1") (pinfunction "1_1") (pintype "passive"))
      (node (ref "D4") (pin "2") (pinfunction "C_2") (pintype "passive"))
      (node (ref "U2") (pin "40") (pinfunction "BOOST1_40") (pintype "power_in"))
    )
    (net (code "21") (name "Net-(L1-Pad2)") (class "Default")
      (node (ref "L1") (pin "2") (pinfunction "2_2") (pintype "passive"))
      (node (ref "R28") (pin "1") (pinfunction "1_1") (pintype "passive"))
      (node (ref "R32") (pin "2") (pinfunction "2_2") (pintype "passive"))
    )
    (net (code "22") (name "Net-(L2-Pad2)") (class "Default")
      (node (ref "L2") (pin "2") (pinfunction "2_2") (pintype "passive"))
      (node (ref "R50") (pin "1") (pinfunction "1_1") (pintype "passive"))
      (node (ref "R53") (pin "2") (pinfunction "2_2") (pintype "passive"))
    )
    (net (code "23") (name "Net-(Q7-E)") (class "Default")
      (node (ref "C31") (pin "1") (pinfunction "1_1") (pintype "passive"))
      (node (ref "Q7") (pin "2") (pinfunction "E_2") (pintype "passive"))
      (node (ref "U2") (pin "6") (pinfunction "TSNS0_6") (pintype "passive"))
    )
    (net (code "24") (name "Net-(Q8-E)") (class "Default")
      (node (ref "C47") (pin "1") (pinfunction "1_1") (pintype "passive"))
      (node (ref "Q8") (pin "2") (pinfunction "E_2") (pintype "passive"))
      (node (ref "U2") (pin "36") (pinfunction "TSNS1_36") (pintype "passive"))
    )
    (net (code "25") (name "Net-(T4-G)") (class "Default")
      (node (ref "C18") (pin "2") (pinfunction "2_2") (pintype "passive"))
      (node (ref "T4") (pin "4") (pinfunction "G_4") (pintype "passive"))
      (node (ref "U2") (pin "2") (pinfunction "TG0_2") (pintype "power_in"))
    )
    (net (code "26") (name "Net-(T5-G)") (class "Default")
      (node (ref "T5") (pin "4") (pinfunction "G_4") (pintype "passive"))
      (node (ref "U2") (pin "50") (pinfunction "BG0_50") (pintype "power_in"))
    )
    (net (code "27") (name "Net-(T6-G)") (class "Default")
      (node (ref "C39") (pin "2") (pinfunction "2_2") (pintype "passive"))
      (node (ref "T6") (pin "4") (pinfunction "G_4") (pintype "passive"))
      (node (ref "U2") (pin "38") (pinfunction "TG1_38") (pintype "power_in"))
    )
    (net (code "28") (name "Net-(T7-G)") (class "Default")
      (node (ref "T7") (pin "4") (pinfunction "G_4") (pintype "passive"))
      (node (ref "U2") (pin "42") (pinfunction "BG1_42") (pintype "power_in"))
    )
    (net (code "29") (name "Net-(U2A-ASEL0)") (class "Default")
      (node (ref "R37") (pin "1") (pinfunction "1_1") (pintype "passive"))
      (node (ref "R40") (pin "2") (pinfunction "2_2") (pintype "passive"))
      (node (ref "U2") (pin "21") (pinfunction "ASEL0_21") (pintype "input"))
    )
    (net (code "30") (name "Net-(U2A-ASEL1)") (class "Default")
      (node (ref "R36") (pin "1") (pinfunction "1_1") (pintype "passive"))
      (node (ref "R39") (pin "2") (pinfunction "2_2") (pintype "passive"))
      (node (ref "U2") (pin "22") (pinfunction "ASEL1_22") (pintype "input"))
    )
    (net (code "31") (name "Net-(U2A-FREQ_CFG)") (class "Default")
      (node (ref "R44") (pin "2") (pinfunction "2_2") (pintype "passive"))
      (node (ref "R46") (pin "1") (pinfunction "1_1") (pintype "passive"))
      (node (ref "U2") (pin "25") (pinfunction "FREQ_CFG_25") (pintype "passive"))
    )
    (net (code "32") (name "Net-(U2A-I_IN+)") (class "Default")
      (node (ref "C17") (pin "1") (pinfunction "1_1") (pintype "passive"))
      (node (ref "C19") (pin "1") (pinfunction "1_1") (pintype "passive"))
      (node (ref "R23") (pin "2") (pinfunction "2_2") (pintype "passive"))
      (node (ref "U2") (pin "47") (pinfunction "I_IN+_47") (pintype "passive"))
    )
    (net (code "33") (name "Net-(U2A-I_IN-)") (class "Default")
      (node (ref "C17") (pin "2") (pinfunction "2_2") (pintype "passive"))
      (node (ref "C20") (pin "1") (pinfunction "1_1") (pintype "passive"))
      (node (ref "R24") (pin "2") (pinfunction "2_2") (pintype "passive"))
      (node (ref "U2") (pin "46") (pinfunction "I_IN-_46") (pintype "passive"))
    )
    (net (code "34") (name "Net-(U2A-PHAS_CFG)") (class "Default")
      (node (ref "R43") (pin "1") (pinfunction "1_1") (pintype "passive"))
      (node (ref "R45") (pin "2") (pinfunction "2_2") (pintype "passive"))
      (node (ref "U2") (pin "26") (pinfunction "PHAS_CFG_26") (pintype "passive"))
    )
    (net (code "35") (name "Net-(U2A-SHARE_CLK)") (class "Default")
      (node (ref "R41") (pin "2") (pinfunction "2_2") (pintype "passive"))
      (node (ref "U2") (pin "29") (pinfunction "SHARE_CLK_29") (pintype "open_collector"))
    )
    (net (code "36") (name "Net-(U2A-SYNC)") (class "Default")
      (node (ref "R42") (pin "2") (pinfunction "2_2") (pintype "passive"))
      (node (ref "U2") (pin "13") (pinfunction "SYNC_13") (pintype "passive"))
    )
    (net (code "37") (name "Net-(U2A-VIN)") (class "Default")
      (node (ref "C27") (pin "1") (pinfunction "1_1") (pintype "passive"))
      (node (ref "R30") (pin "2") (pinfunction "2_2") (pintype "passive"))
      (node (ref "U2") (pin "48") (pinfunction "VIN_48") (pintype "power_in"))
    )
    (net (code "38") (name "Net-(U2A-WP)") (class "Default")
      (node (ref "R38") (pin "1") (pinfunction "1_1") (pintype "passive"))
      (node (ref "U2") (pin "28") (pinfunction "WP_28") (pintype "input"))
    )
    (net (code "39") (name "Net-(U2B-ITH0)") (class "Default")
      (node (ref "C32") (pin "1") (pinfunction "1_1") (pintype "passive"))
      (node (ref "U2") (pin "12") (pinfunction "ITH0_12") (pintype "passive"))
    )
    (net (code "40") (name "Net-(U2B-ITHR0)") (class "Default")
      (node (ref "C33") (pin "1") (pinfunction "1_1") (pintype "passive"))
      (node (ref "U2") (pin "11") (pinfunction "ITHR0_11") (pintype "passive"))
    )
    (net (code "41") (name "Net-(U2B-I_SENSE_0+)") (class "Default")
      (node (ref "C30") (pin "1") (pinfunction "1_1") (pintype "passive"))
      (node (ref "R32") (pin "1") (pinfunction "1_1") (pintype "passive"))
      (node (ref "U2") (pin "4") (pinfunction "I_SENSE_0+_4") (pintype "passive"))
    )
    (net (code "42") (name "Net-(U2B-I_SENSE_0-)") (class "Default")
      (node (ref "C30") (pin "2") (pinfunction "2_2") (pintype "passive"))
      (node (ref "R34") (pin "1") (pinfunction "1_1") (pintype "passive"))
      (node (ref "U2") (pin "5") (pinfunction "I_SENSE_0-_5") (pintype "passive"))
    )
    (net (code "43") (name "Net-(U2B-SW0)") (class "Default")
      (node (ref "L1") (pin "1") (pinfunction "1_1") (pintype "passive"))
      (node (ref "T4") (pin "1") (pinfunction "S_1") (pintype "passive"))
      (node (ref "T4") (pin "2") (pinfunction "S_2") (pintype "passive"))
      (node (ref "T4") (pin "3") (pinfunction "S_3") (pintype "passive"))
      (node (ref "T5") (pin "5") (pinfunction "D_5") (pintype "passive"))
      (node (ref "T5") (pin "6") (pinfunction "D_6") (pintype "passive"))
      (node (ref "T5") (pin "7") (pinfunction "D_7") (pintype "passive"))
      (node (ref "T5") (pin "8") (pinfunction "D_8") (pintype "passive"))
      (node (ref "U2") (pin "1") (pinfunction "SW0_1") (pintype "power_in"))
    )
    (net (code "44") (name "Net-(U2B-VOUT_CFG0)") (class "Default")
      (node (ref "R31") (pin "1") (pinfunction "1_1") (pintype "passive"))
      (node (ref "R35") (pin "1") (pinfunction "1_1") (pintype "passive"))
      (node (ref "U2") (pin "23") (pinfunction "VOUT_CFG0_23") (pintype "passive"))
    )
    (net (code "45") (name "Net-(U2B-V_SENSE_0+)") (class "Default")
      (node (ref "R29") (pin "1") (pinfunction "1_1") (pintype "passive"))
      (node (ref "U2") (pin "7") (pinfunction "V_SENSE_0+_7") (pintype "passive"))
    )
    (net (code "46") (name "Net-(U2C-ITH1)") (class "Default")
      (node (ref "C48") (pin "1") (pinfunction "1_1") (pintype "passive"))
      (node (ref "U2") (pin "31") (pinfunction "ITH1_31") (pintype "passive"))
    )
    (net (code "47") (name "Net-(U2C-ITHR1)") (class "Default")
      (node (ref "C49") (pin "1") (pinfunction "1_1") (pintype "passive"))
      (node (ref "U2") (pin "32") (pinfunction "ITHR1_32") (pintype "passive"))
    )
    (net (code "48") (name "Net-(U2C-I_SENSE_1+)") (class "Default")
      (node (ref "C46") (pin "1") (pinfunction "1_1") (pintype "passive"))
      (node (ref "R53") (pin "1") (pinfunction "1_1") (pintype "passive"))
      (node (ref "U2") (pin "9") (pinfunction "I_SENSE_1+_9") (pintype "passive"))
    )
    (net (code "49") (name "Net-(U2C-I_SENSE_1-)") (class "Default")
      (node (ref "C46") (pin "2") (pinfunction "2_2") (pintype "passive"))
      (node (ref "R54") (pin "1") (pinfunction "1_1") (pintype "passive"))
      (node (ref "U2") (pin "10") (pinfunction "I_SENSE_1-_10") (pintype "passive"))
    )
    (net (code "50") (name "Net-(U2C-SW1)") (class "Default")
      (node (ref "L2") (pin "1") (pinfunction "1_1") (pintype "passive"))
      (node (ref "T6") (pin "1") (pinfunction "S_1") (pintype "passive"))
      (node (ref "T6") (pin "2") (pinfunction "S_2") (pintype "passive"))
      (node (ref "T6") (pin "3") (pinfunction "S_3") (pintype "passive"))
      (node (ref "T7") (pin "5") (pinfunction "D_5") (pintype "passive"))
      (node (ref "T7") (pin "6") (pinfunction "D_6") (pintype "passive"))
      (node (ref "T7") (pin "7") (pinfunction "D_7") (pintype "passive"))
      (node (ref "T7") (pin "8") (pinfunction "D_8") (pintype "passive"))
      (node (ref "U2") (pin "39") (pinfunction "SW1_39") (pintype "power_in"))
    )
    (net (code "51") (name "Net-(U2C-VOUT_CFG1)") (class "Default")
      (node (ref "R52") (pin "2") (pinfunction "2_2") (pintype "passive"))
      (node (ref "R55") (pin "1") (pinfunction "1_1") (pintype "passive"))
      (node (ref "U2") (pin "24") (pinfunction "VOUT_CFG1_24") (pintype "passive"))
    )
    (net (code "52") (name "Net-(U2C-V_SENSE_1+)") (class "Default")
      (node (ref "R51") (pin "1") (pinfunction "1_1") (pintype "passive"))
      (node (ref "U2") (pin "35") (pinfunction "V_SENSE_1+_35") (pintype "passive"))
    )
    (net (code "53") (name "unconnected-(J15-Pad7)") (class "Default")
      (node (ref "J15") (pin "7") (pinfunction "7_7") (pintype "passive+no_connect"))
    )
    (net (code "54") (name "unconnected-(J15-Pad8)") (class "Default")
      (node (ref "J15") (pin "8") (pinfunction "8_8") (pintype "passive+no_connect"))
    )
    (net (code "55") (name "unconnected-(J15-Pad9)") (class "Default")
      (node (ref "J15") (pin "9") (pinfunction "9_9") (pintype "passive"))
    )
    (net (code "56") (name "unconnected-(J15-Pad11)") (class "Default")
      (node (ref "J15") (pin "11") (pinfunction "11_11") (pintype "passive+no_connect"))
    )
    (net (code "57") (name "unconnected-(J15-Pad12)") (class "Default")
      (node (ref "J15") (pin "12") (pinfunction "12_12") (pintype "passive+no_connect"))
    )
  )
)
